# Clock_Schematic_v_3.net
KiCad netlist of a schematic drawn in EAGLE
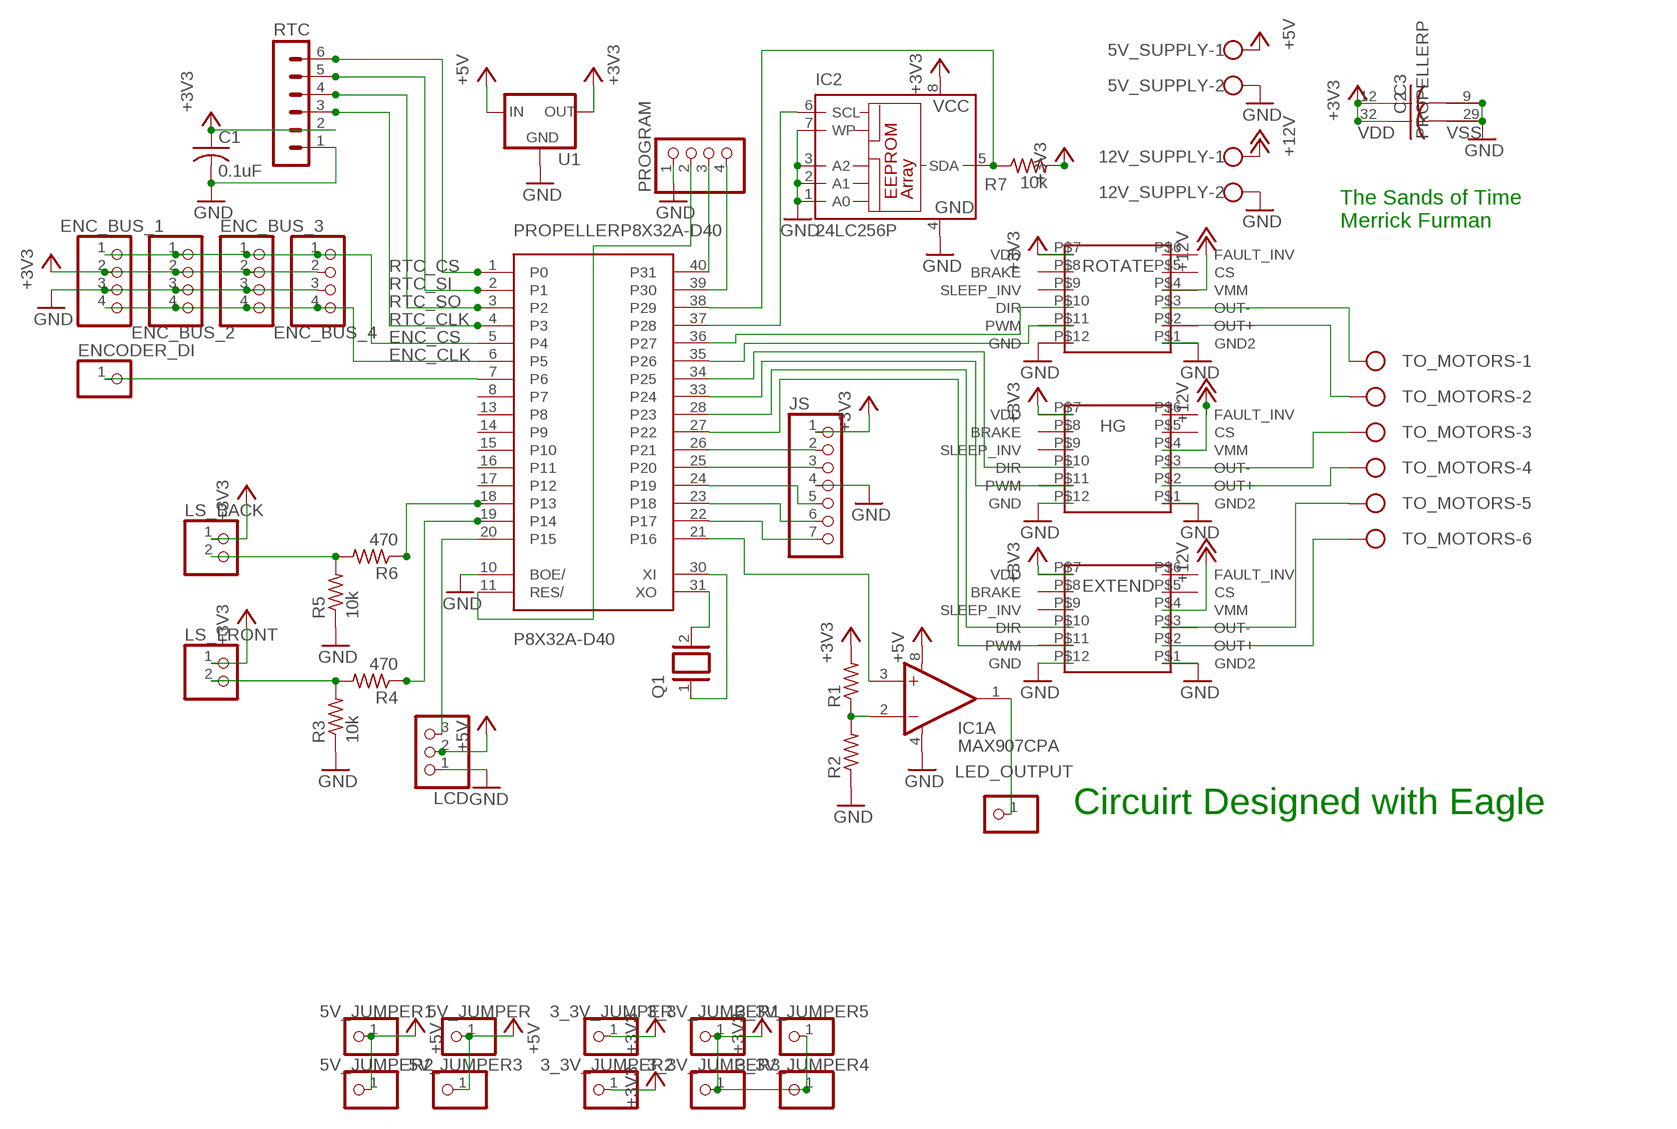
[diagram p0: schematic, sheet 1]

(export (version "E")
  (design (tool "Eeschema 10.0.6"))
  (components
    (comp (ref "3_3V_JUMPER")
      (value "PINHD-1X1")
      (footprint "eagle-import:1X01")
      (libsource (lib "eagle-import") (part "PINHD-1X1"))
    )
    (comp (ref "3_3V_JUMPER1")
      (value "PINHD-1X1")
      (footprint "eagle-import:1X01")
      (libsource (lib "eagle-import") (part "PINHD-1X1"))
    )
    (comp (ref "3_3V_JUMPER2")
      (value "PINHD-1X1")
      (footprint "eagle-import:1X01")
      (libsource (lib "eagle-import") (part "PINHD-1X1"))
    )
    (comp (ref "3_3V_JUMPER3")
      (value "PINHD-1X1")
      (footprint "eagle-import:1X01")
      (libsource (lib "eagle-import") (part "PINHD-1X1"))
    )
    (comp (ref "3_3V_JUMPER4")
      (value "PINHD-1X1")
      (footprint "eagle-import:1X01")
      (libsource (lib "eagle-import") (part "PINHD-1X1"))
    )
    (comp (ref "3_3V_JUMPER5")
      (value "PINHD-1X1")
      (footprint "eagle-import:1X01")
      (libsource (lib "eagle-import") (part "PINHD-1X1"))
    )
    (comp (ref "5V_JUMPER")
      (value "PINHD-1X1")
      (footprint "eagle-import:1X01")
      (libsource (lib "eagle-import") (part "PINHD-1X1"))
    )
    (comp (ref "5V_JUMPER1")
      (value "PINHD-1X1")
      (footprint "eagle-import:1X01")
      (libsource (lib "eagle-import") (part "PINHD-1X1"))
    )
    (comp (ref "5V_JUMPER2")
      (value "PINHD-1X1")
      (footprint "eagle-import:1X01")
      (libsource (lib "eagle-import") (part "PINHD-1X1"))
    )
    (comp (ref "5V_JUMPER3")
      (value "PINHD-1X1")
      (footprint "eagle-import:1X01")
      (libsource (lib "eagle-import") (part "PINHD-1X1"))
    )
    (comp (ref "5V_SUPPLY")
      (value "W237-102")
      (footprint "eagle-import:W237-102")
      (fields (field (name "MPN") "237-102"))
      (libsource (lib "eagle-import") (part "W237-102"))
    )
    (comp (ref "12V_SUPPLY")
      (value "W237-102")
      (footprint "eagle-import:W237-102")
      (fields (field (name "MPN") "237-102"))
      (libsource (lib "eagle-import") (part "W237-102"))
    )
    (comp (ref "C1")
      (value "0.1uF")
      (footprint "eagle-import:C050-025X075")
      (libsource (lib "eagle-import") (part "C-US050-025X075"))
    )
    (comp (ref "C2")
      (value "C-US050-025X075")
      (footprint "eagle-import:C050-025X075")
      (libsource (lib "eagle-import") (part "C-US050-025X075"))
    )
    (comp (ref "C3")
      (value "C-US050-025X075")
      (footprint "eagle-import:C050-025X075")
      (libsource (lib "eagle-import") (part "C-US050-025X075"))
    )
    (comp (ref "ENCODER_DI")
      (value "PINHD-1X1")
      (footprint "eagle-import:1X01")
      (libsource (lib "eagle-import") (part "PINHD-1X1"))
    )
    (comp (ref "ENC_BUS_1")
      (value "PINHD-1X4")
      (footprint "eagle-import:1X04")
      (libsource (lib "eagle-import") (part "PINHD-1X4"))
    )
    (comp (ref "ENC_BUS_2")
      (value "PINHD-1X4")
      (footprint "eagle-import:1X04")
      (libsource (lib "eagle-import") (part "PINHD-1X4"))
    )
    (comp (ref "ENC_BUS_3")
      (value "PINHD-1X4")
      (footprint "eagle-import:1X04")
      (libsource (lib "eagle-import") (part "PINHD-1X4"))
    )
    (comp (ref "ENC_BUS_4")
      (value "PINHD-1X4")
      (footprint "eagle-import:1X04")
      (libsource (lib "eagle-import") (part "PINHD-1X4"))
    )
    (comp (ref "EXTEND")
      (value "DRV")
      (footprint "eagle-import:DRV")
      (libsource (lib "eagle-import") (part "DRV"))
    )
    (comp (ref "HG")
      (value "DRV")
      (footprint "eagle-import:DRV")
      (libsource (lib "eagle-import") (part "DRV"))
    )
    (comp (ref "IC1")
      (value "MAX907CPA")
      (footprint "eagle-import:DIL08")
      (fields (field (name "MF") "MAXIM"))
      (libsource (lib "eagle-import") (part "MAX907CPA"))
    )
    (comp (ref "IC2")
      (value "24LC256P")
      (footprint "eagle-import:DIL8")
      (fields (field (name "MF") "MICROCHIP") (field (name "MPN") "24LC256-E/P"))
      (libsource (lib "eagle-import") (part "24PLC256"))
    )
    (comp (ref "JS")
      (value "PINHD-1X7")
      (footprint "eagle-import:1X07")
      (libsource (lib "eagle-import") (part "PINHD-1X7"))
    )
    (comp (ref "LCD")
      (value "PINHD-1X3")
      (footprint "eagle-import:1X03")
      (libsource (lib "eagle-import") (part "PINHD-1X3"))
    )
    (comp (ref "LED_OUTPUT")
      (value "PINHD-1X1")
      (footprint "eagle-import:1X01")
      (libsource (lib "eagle-import") (part "PINHD-1X1"))
    )
    (comp (ref "LS_BACK")
      (value "PINHD-1X2")
      (footprint "eagle-import:1X02")
      (libsource (lib "eagle-import") (part "PINHD-1X2"))
    )
    (comp (ref "LS_FRONT")
      (value "PINHD-1X2")
      (footprint "eagle-import:1X02")
      (libsource (lib "eagle-import") (part "PINHD-1X2"))
    )
    (comp (ref "PROGRAM")
      (value "PINHD-1X4")
      (footprint "eagle-import:1X04")
      (libsource (lib "eagle-import") (part "PINHD-1X4"))
    )
    (comp (ref "PROPELLER")
      (value "P8X32A-D40")
      (footprint "eagle-import:P8X32A-D40")
      (libsource (lib "eagle-import") (part "P8X32A-D40"))
    )
    (comp (ref "Q1")
      (value "XTAL/S")
      (footprint "eagle-import:QS")
      (libsource (lib "eagle-import") (part "XTAL/S"))
    )
    (comp (ref "R1")
      (value "R-US_0207/10")
      (footprint "eagle-import:0207_10")
      (libsource (lib "eagle-import") (part "R-US_0207/10"))
    )
    (comp (ref "R2")
      (value "R-US_0207/10")
      (footprint "eagle-import:0207_10")
      (libsource (lib "eagle-import") (part "R-US_0207/10"))
    )
    (comp (ref "R3")
      (value "10k")
      (footprint "eagle-import:0207_10")
      (libsource (lib "eagle-import") (part "R-US_0207/10"))
    )
    (comp (ref "R4")
      (value "470")
      (footprint "eagle-import:0207_10")
      (libsource (lib "eagle-import") (part "R-US_0207/10"))
    )
    (comp (ref "R5")
      (value "10k")
      (footprint "eagle-import:0207_10")
      (libsource (lib "eagle-import") (part "R-US_0207/10"))
    )
    (comp (ref "R6")
      (value "470")
      (footprint "eagle-import:0207_10")
      (libsource (lib "eagle-import") (part "R-US_0207/10"))
    )
    (comp (ref "R7")
      (value "10k")
      (footprint "eagle-import:0207_10")
      (libsource (lib "eagle-import") (part "R-US_0207/10"))
    )
    (comp (ref "ROTATE")
      (value "DRV")
      (footprint "eagle-import:DRV")
      (libsource (lib "eagle-import") (part "DRV"))
    )
    (comp (ref "RTC")
      (value "MA06-1")
      (footprint "eagle-import:MA06-1")
      (libsource (lib "eagle-import") (part "MA06-1"))
    )
    (comp (ref "TO_MOTORS")
      (value "W237-6")
      (footprint "eagle-import:W237-6")
      (libsource (lib "eagle-import") (part "W237-6"))
    )
    (comp (ref "U1")
      (value "V_REG_78XXSIDE")
      (footprint "eagle-import:78XXL")
      (libsource (lib "eagle-import") (part "V_REG_78XXSIDE"))
    )
  )
  (nets
    (net (code "1") (name "+3V3") (class "Default")
      (node (ref "3_3V_JUMPER") (pin "1") (pinfunction "1_1") (pintype "passive"))
      (node (ref "3_3V_JUMPER1") (pin "1") (pinfunction "1_1") (pintype "passive"))
      (node (ref "3_3V_JUMPER2") (pin "1") (pinfunction "1_1") (pintype "passive"))
      (node (ref "3_3V_JUMPER3") (pin "1") (pinfunction "1_1") (pintype "passive"))
      (node (ref "3_3V_JUMPER4") (pin "1") (pinfunction "1_1") (pintype "passive"))
      (node (ref "3_3V_JUMPER5") (pin "1") (pinfunction "1_1") (pintype "passive"))
      (node (ref "C1") (pin "1") (pinfunction "1_1") (pintype "passive"))
      (node (ref "C2") (pin "1") (pinfunction "1_1") (pintype "passive"))
      (node (ref "C3") (pin "1") (pinfunction "1_1") (pintype "passive"))
      (node (ref "ENC_BUS_1") (pin "2") (pinfunction "2_2") (pintype "passive"))
      (node (ref "ENC_BUS_2") (pin "2") (pinfunction "2_2") (pintype "passive"))
      (node (ref "ENC_BUS_3") (pin "2") (pinfunction "2_2") (pintype "passive"))
      (node (ref "ENC_BUS_4") (pin "2") (pinfunction "2_2") (pintype "passive"))
      (node (ref "EXTEND") (pin "P$7") (pinfunction "VDD_P$7") (pintype "bidirectional"))
      (node (ref "HG") (pin "P$7") (pinfunction "VDD_P$7") (pintype "bidirectional"))
      (node (ref "IC2") (pin "8") (pinfunction "VCC_8") (pintype "power_in"))
      (node (ref "JS") (pin "1") (pinfunction "1_1") (pintype "passive"))
      (node (ref "LS_BACK") (pin "1") (pinfunction "1_1") (pintype "passive"))
      (node (ref "LS_FRONT") (pin "1") (pinfunction "1_1") (pintype "passive"))
      (node (ref "PROPELLER") (pin "12") (pinfunction "VDD_12") (pintype "power_in"))
      (node (ref "PROPELLER") (pin "32") (pinfunction "VDD_32") (pintype "power_in"))
      (node (ref "R1") (pin "2") (pinfunction "2_2") (pintype "passive"))
      (node (ref "R7") (pin "2") (pinfunction "2_2") (pintype "passive"))
      (node (ref "ROTATE") (pin "P$7") (pinfunction "VDD_P$7") (pintype "bidirectional"))
      (node (ref "RTC") (pin "2") (pinfunction "2_2") (pintype "passive"))
      (node (ref "U1") (pin "OUT") (pinfunction "OUT_OUT") (pintype "passive"))
    )
    (net (code "2") (name "+5V") (class "Default")
      (node (ref "5V_JUMPER") (pin "1") (pinfunction "1_1") (pintype "passive"))
      (node (ref "5V_JUMPER1") (pin "1") (pinfunction "1_1") (pintype "passive"))
      (node (ref "5V_JUMPER2") (pin "1") (pinfunction "1_1") (pintype "passive"))
      (node (ref "5V_JUMPER3") (pin "1") (pinfunction "1_1") (pintype "passive"))
      (node (ref "5V_SUPPLY") (pin "1") (pinfunction "KL_1") (pintype "passive"))
      (node (ref "IC1") (pin "8") (pinfunction "V+_8") (pintype "power_in"))
      (node (ref "LCD") (pin "2") (pinfunction "2_2") (pintype "passive"))
      (node (ref "U1") (pin "IN") (pinfunction "IN_IN") (pintype "input"))
    )
    (net (code "3") (name "+12V") (class "Default")
      (node (ref "12V_SUPPLY") (pin "1") (pinfunction "KL_1") (pintype "passive"))
      (node (ref "EXTEND") (pin "P$4") (pinfunction "VMM_P$4") (pintype "bidirectional"))
      (node (ref "HG") (pin "P$4") (pinfunction "VMM_P$4") (pintype "bidirectional"))
      (node (ref "ROTATE") (pin "P$4") (pinfunction "VMM_P$4") (pintype "bidirectional"))
    )
    (net (code "4") (name "/ENC_CLK") (class "Default")
      (node (ref "ENC_BUS_1") (pin "4") (pinfunction "4_4") (pintype "passive"))
      (node (ref "ENC_BUS_2") (pin "4") (pinfunction "4_4") (pintype "passive"))
      (node (ref "ENC_BUS_3") (pin "4") (pinfunction "4_4") (pintype "passive"))
      (node (ref "ENC_BUS_4") (pin "4") (pinfunction "4_4") (pintype "passive"))
      (node (ref "PROPELLER") (pin "6") (pinfunction "P5_6") (pintype "bidirectional"))
    )
    (net (code "5") (name "/ENC_CS") (class "Default")
      (node (ref "ENC_BUS_1") (pin "1") (pinfunction "1_1") (pintype "passive"))
      (node (ref "ENC_BUS_2") (pin "1") (pinfunction "1_1") (pintype "passive"))
      (node (ref "ENC_BUS_3") (pin "1") (pinfunction "1_1") (pintype "passive"))
      (node (ref "ENC_BUS_4") (pin "1") (pinfunction "1_1") (pintype "passive"))
      (node (ref "PROPELLER") (pin "5") (pinfunction "P4_5") (pintype "bidirectional"))
    )
    (net (code "6") (name "/RTC_CLK") (class "Default")
      (node (ref "PROPELLER") (pin "4") (pinfunction "P3_4") (pintype "bidirectional"))
      (node (ref "RTC") (pin "3") (pinfunction "3_3") (pintype "passive"))
    )
    (net (code "7") (name "/RTC_CS") (class "Default")
      (node (ref "PROPELLER") (pin "1") (pinfunction "P0_1") (pintype "bidirectional"))
      (node (ref "RTC") (pin "6") (pinfunction "6_6") (pintype "passive"))
    )
    (net (code "8") (name "/RTC_SI") (class "Default")
      (node (ref "PROPELLER") (pin "2") (pinfunction "P1_2") (pintype "bidirectional"))
      (node (ref "RTC") (pin "5") (pinfunction "5_5") (pintype "passive"))
    )
    (net (code "9") (name "/RTC_SO") (class "Default")
      (node (ref "PROPELLER") (pin "3") (pinfunction "P2_3") (pintype "bidirectional"))
      (node (ref "RTC") (pin "4") (pinfunction "4_4") (pintype "passive"))
    )
    (net (code "10") (name "GND") (class "Default")
      (node (ref "12V_SUPPLY") (pin "2") (pinfunction "KL_2") (pintype "passive"))
      (node (ref "5V_SUPPLY") (pin "2") (pinfunction "KL_2") (pintype "passive"))
      (node (ref "C1") (pin "2") (pinfunction "2_2") (pintype "passive"))
      (node (ref "C2") (pin "2") (pinfunction "2_2") (pintype "passive"))
      (node (ref "C3") (pin "2") (pinfunction "2_2") (pintype "passive"))
      (node (ref "ENC_BUS_1") (pin "3") (pinfunction "3_3") (pintype "passive"))
      (node (ref "ENC_BUS_2") (pin "3") (pinfunction "3_3") (pintype "passive"))
      (node (ref "ENC_BUS_3") (pin "3") (pinfunction "3_3") (pintype "passive"))
      (node (ref "ENC_BUS_4") (pin "3") (pinfunction "3_3") (pintype "passive"))
      (node (ref "EXTEND") (pin "P$1") (pinfunction "GND2_P$1") (pintype "bidirectional"))
      (node (ref "EXTEND") (pin "P$12") (pinfunction "GND_P$12") (pintype "bidirectional"))
      (node (ref "HG") (pin "P$1") (pinfunction "GND2_P$1") (pintype "bidirectional"))
      (node (ref "HG") (pin "P$12") (pinfunction "GND_P$12") (pintype "bidirectional"))
      (node (ref "IC1") (pin "4") (pinfunction "V-_4") (pintype "power_in"))
      (node (ref "IC2") (pin "1") (pinfunction "A0_1") (pintype "input"))
      (node (ref "IC2") (pin "2") (pinfunction "A1_2") (pintype "input"))
      (node (ref "IC2") (pin "3") (pinfunction "A2_3") (pintype "input"))
      (node (ref "IC2") (pin "4") (pinfunction "GND_4") (pintype "power_in"))
      (node (ref "IC2") (pin "7") (pinfunction "WP_7") (pintype "input"))
      (node (ref "JS") (pin "4") (pinfunction "4_4") (pintype "passive"))
      (node (ref "LCD") (pin "1") (pinfunction "1_1") (pintype "passive"))
      (node (ref "PROGRAM") (pin "1") (pinfunction "1_1") (pintype "passive"))
      (node (ref "PROPELLER") (pin "10") (pinfunction "BOE/_10") (pintype "input"))
      (node (ref "PROPELLER") (pin "29") (pinfunction "VSS_29") (pintype "power_in"))
      (node (ref "PROPELLER") (pin "9") (pinfunction "VSS_9") (pintype "power_in"))
      (node (ref "R2") (pin "1") (pinfunction "1_1") (pintype "passive"))
      (node (ref "R3") (pin "1") (pinfunction "1_1") (pintype "passive"))
      (node (ref "R5") (pin "1") (pinfunction "1_1") (pintype "passive"))
      (node (ref "ROTATE") (pin "P$1") (pinfunction "GND2_P$1") (pintype "bidirectional"))
      (node (ref "ROTATE") (pin "P$12") (pinfunction "GND_P$12") (pintype "bidirectional"))
      (node (ref "RTC") (pin "1") (pinfunction "1_1") (pintype "passive"))
      (node (ref "U1") (pin "GND") (pinfunction "GND_GND") (pintype "input"))
    )
    (net (code "11") (name "Net-(EXTEND-DIR)") (class "Default")
      (node (ref "EXTEND") (pin "P$10") (pinfunction "DIR_P$10") (pintype "bidirectional"))
      (node (ref "PROPELLER") (pin "28") (pinfunction "P23_28") (pintype "bidirectional"))
    )
    (net (code "12") (name "Net-(EXTEND-OUT+)") (class "Default")
      (node (ref "EXTEND") (pin "P$2") (pinfunction "OUT+_P$2") (pintype "bidirectional"))
      (node (ref "TO_MOTORS") (pin "6") (pinfunction "KL_6") (pintype "passive"))
    )
    (net (code "13") (name "Net-(EXTEND-OUT-)") (class "Default")
      (node (ref "EXTEND") (pin "P$3") (pinfunction "OUT-_P$3") (pintype "bidirectional"))
      (node (ref "TO_MOTORS") (pin "5") (pinfunction "KL_5") (pintype "passive"))
    )
    (net (code "14") (name "Net-(EXTEND-PWM)") (class "Default")
      (node (ref "EXTEND") (pin "P$11") (pinfunction "PWM_P$11") (pintype "bidirectional"))
      (node (ref "PROPELLER") (pin "27") (pinfunction "P22_27") (pintype "bidirectional"))
    )
    (net (code "15") (name "Net-(HG-DIR)") (class "Default")
      (node (ref "HG") (pin "P$10") (pinfunction "DIR_P$10") (pintype "bidirectional"))
      (node (ref "PROPELLER") (pin "34") (pinfunction "P25_34") (pintype "bidirectional"))
    )
    (net (code "16") (name "Net-(HG-OUT+)") (class "Default")
      (node (ref "HG") (pin "P$2") (pinfunction "OUT+_P$2") (pintype "bidirectional"))
      (node (ref "TO_MOTORS") (pin "4") (pinfunction "KL_4") (pintype "passive"))
    )
    (net (code "17") (name "Net-(HG-OUT-)") (class "Default")
      (node (ref "HG") (pin "P$3") (pinfunction "OUT-_P$3") (pintype "bidirectional"))
      (node (ref "TO_MOTORS") (pin "3") (pinfunction "KL_3") (pintype "passive"))
    )
    (net (code "18") (name "Net-(HG-PWM)") (class "Default")
      (node (ref "HG") (pin "P$11") (pinfunction "PWM_P$11") (pintype "bidirectional"))
      (node (ref "PROPELLER") (pin "33") (pinfunction "P24_33") (pintype "bidirectional"))
    )
    (net (code "19") (name "Net-(IC1A-+IN)") (class "Default")
      (node (ref "IC1") (pin "3") (pinfunction "+IN_3") (pintype "input"))
      (node (ref "PROPELLER") (pin "21") (pinfunction "P16_21") (pintype "bidirectional"))
    )
    (net (code "20") (name "Net-(IC1A--IN)") (class "Default")
      (node (ref "IC1") (pin "2") (pinfunction "-IN_2") (pintype "input"))
      (node (ref "R1") (pin "1") (pinfunction "1_1") (pintype "passive"))
      (node (ref "R2") (pin "2") (pinfunction "2_2") (pintype "passive"))
    )
    (net (code "21") (name "Net-(IC1A-OUT)") (class "Default")
      (node (ref "IC1") (pin "1") (pinfunction "OUT_1") (pintype "output"))
      (node (ref "LED_OUTPUT") (pin "1") (pinfunction "1_1") (pintype "passive"))
    )
    (net (code "22") (name "Net-(IC2-SCL)") (class "Default")
      (node (ref "IC2") (pin "6") (pinfunction "SCL_6") (pintype "input"))
      (node (ref "PROPELLER") (pin "37") (pinfunction "P28_37") (pintype "bidirectional"))
    )
    (net (code "23") (name "Net-(IC2-SDA)") (class "Default")
      (node (ref "IC2") (pin "5") (pinfunction "SDA_5") (pintype "bidirectional"))
      (node (ref "PROPELLER") (pin "38") (pinfunction "P29_38") (pintype "bidirectional"))
      (node (ref "R7") (pin "1") (pinfunction "1_1") (pintype "passive"))
    )
    (net (code "24") (name "Net-(LS_BACK-Pad2)") (class "Default")
      (node (ref "LS_BACK") (pin "2") (pinfunction "2_2") (pintype "passive"))
      (node (ref "R5") (pin "2") (pinfunction "2_2") (pintype "passive"))
      (node (ref "R6") (pin "2") (pinfunction "2_2") (pintype "passive"))
    )
    (net (code "25") (name "Net-(LS_FRONT-Pad2)") (class "Default")
      (node (ref "LS_FRONT") (pin "2") (pinfunction "2_2") (pintype "passive"))
      (node (ref "R3") (pin "2") (pinfunction "2_2") (pintype "passive"))
      (node (ref "R4") (pin "2") (pinfunction "2_2") (pintype "passive"))
    )
    (net (code "26") (name "Net-(PROPELLERB-P6)") (class "Default")
      (node (ref "ENCODER_DI") (pin "1") (pinfunction "1_1") (pintype "passive"))
      (node (ref "PROPELLER") (pin "7") (pinfunction "P6_7") (pintype "bidirectional"))
    )
    (net (code "27") (name "Net-(PROPELLERB-P13)") (class "Default")
      (node (ref "PROPELLER") (pin "18") (pinfunction "P13_18") (pintype "bidirectional"))
      (node (ref "R6") (pin "1") (pinfunction "1_1") (pintype "passive"))
    )
    (net (code "28") (name "Net-(PROPELLERB-P14)") (class "Default")
      (node (ref "PROPELLER") (pin "19") (pinfunction "P14_19") (pintype "bidirectional"))
      (node (ref "R4") (pin "1") (pinfunction "1_1") (pintype "passive"))
    )
    (net (code "29") (name "Net-(PROPELLERB-P15)") (class "Default")
      (node (ref "LCD") (pin "3") (pinfunction "3_3") (pintype "passive"))
      (node (ref "PROPELLER") (pin "20") (pinfunction "P15_20") (pintype "bidirectional"))
    )
    (net (code "30") (name "Net-(PROPELLERB-P17)") (class "Default")
      (node (ref "JS") (pin "7") (pinfunction "7_7") (pintype "passive"))
      (node (ref "PROPELLER") (pin "22") (pinfunction "P17_22") (pintype "bidirectional"))
    )
    (net (code "31") (name "Net-(PROPELLERB-P18)") (class "Default")
      (node (ref "JS") (pin "6") (pinfunction "6_6") (pintype "passive"))
      (node (ref "PROPELLER") (pin "23") (pinfunction "P18_23") (pintype "bidirectional"))
    )
    (net (code "32") (name "Net-(PROPELLERB-P19)") (class "Default")
      (node (ref "JS") (pin "5") (pinfunction "5_5") (pintype "passive"))
      (node (ref "PROPELLER") (pin "24") (pinfunction "P19_24") (pintype "bidirectional"))
    )
    (net (code "33") (name "Net-(PROPELLERB-P20)") (class "Default")
      (node (ref "JS") (pin "3") (pinfunction "3_3") (pintype "passive"))
      (node (ref "PROPELLER") (pin "25") (pinfunction "P20_25") (pintype "bidirectional"))
    )
    (net (code "34") (name "Net-(PROPELLERB-P21)") (class "Default")
      (node (ref "JS") (pin "2") (pinfunction "2_2") (pintype "passive"))
      (node (ref "PROPELLER") (pin "26") (pinfunction "P21_26") (pintype "bidirectional"))
    )
    (net (code "35") (name "Net-(PROPELLERB-P26)") (class "Default")
      (node (ref "PROPELLER") (pin "35") (pinfunction "P26_35") (pintype "bidirectional"))
      (node (ref "ROTATE") (pin "P$11") (pinfunction "PWM_P$11") (pintype "bidirectional"))
    )
    (net (code "36") (name "Net-(PROPELLERB-P27)") (class "Default")
      (node (ref "PROPELLER") (pin "36") (pinfunction "P27_36") (pintype "bidirectional"))
      (node (ref "ROTATE") (pin "P$10") (pinfunction "DIR_P$10") (pintype "bidirectional"))
    )
    (net (code "37") (name "Net-(PROPELLERB-P30)") (class "Default")
      (node (ref "PROGRAM") (pin "4") (pinfunction "4_4") (pintype "passive"))
      (node (ref "PROPELLER") (pin "39") (pinfunction "P30_39") (pintype "bidirectional"))
    )
    (net (code "38") (name "Net-(PROPELLERB-P31)") (class "Default")
      (node (ref "PROGRAM") (pin "3") (pinfunction "3_3") (pintype "passive"))
      (node (ref "PROPELLER") (pin "40") (pinfunction "P31_40") (pintype "bidirectional"))
    )
    (net (code "39") (name "Net-(PROPELLERB-RES{slash})") (class "Default")
      (node (ref "PROGRAM") (pin "2") (pinfunction "2_2") (pintype "passive"))
      (node (ref "PROPELLER") (pin "11") (pinfunction "RES/_11") (pintype "bidirectional"))
    )
    (net (code "40") (name "Net-(PROPELLERB-XI)") (class "Default")
      (node (ref "PROPELLER") (pin "30") (pinfunction "XI_30") (pintype "input"))
      (node (ref "Q1") (pin "1") (pinfunction "1_1") (pintype "passive"))
    )
    (net (code "41") (name "Net-(PROPELLERB-XO)") (class "Default")
      (node (ref "PROPELLER") (pin "31") (pinfunction "XO_31") (pintype "output"))
      (node (ref "Q1") (pin "2") (pinfunction "2_2") (pintype "passive"))
    )
    (net (code "42") (name "Net-(ROTATE-OUT+)") (class "Default")
      (node (ref "ROTATE") (pin "P$2") (pinfunction "OUT+_P$2") (pintype "bidirectional"))
      (node (ref "TO_MOTORS") (pin "2") (pinfunction "KL_2") (pintype "passive"))
    )
    (net (code "43") (name "Net-(ROTATE-OUT-)") (class "Default")
      (node (ref "ROTATE") (pin "P$3") (pinfunction "OUT-_P$3") (pintype "bidirectional"))
      (node (ref "TO_MOTORS") (pin "1") (pinfunction "KL_1") (pintype "passive"))
    )
    (net (code "44") (name "unconnected-(EXTEND-BRAKE-PadP$8)") (class "Default")
      (node (ref "EXTEND") (pin "P$8") (pinfunction "BRAKE_P$8") (pintype "bidirectional"))
    )
    (net (code "45") (name "unconnected-(EXTEND-CS-PadP$5)") (class "Default")
      (node (ref "EXTEND") (pin "P$5") (pinfunction "CS_P$5") (pintype "bidirectional"))
    )
    (net (code "46") (name "unconnected-(EXTEND-FAULT_INV-PadP$6)") (class "Default")
      (node (ref "EXTEND") (pin "P$6") (pinfunction "FAULT_INV_P$6") (pintype "bidirectional"))
    )
    (net (code "47") (name "unconnected-(EXTEND-SLEEP_INV-PadP$9)") (class "Default")
      (node (ref "EXTEND") (pin "P$9") (pinfunction "SLEEP_INV_P$9") (pintype "bidirectional"))
    )
    (net (code "48") (name "unconnected-(HG-BRAKE-PadP$8)") (class "Default")
      (node (ref "HG") (pin "P$8") (pinfunction "BRAKE_P$8") (pintype "bidirectional"))
    )
    (net (code "49") (name "unconnected-(HG-CS-PadP$5)") (class "Default")
      (node (ref "HG") (pin "P$5") (pinfunction "CS_P$5") (pintype "bidirectional"))
    )
    (net (code "50") (name "unconnected-(HG-FAULT_INV-PadP$6)") (class "Default")
      (node (ref "HG") (pin "P$6") (pinfunction "FAULT_INV_P$6") (pintype "bidirectional"))
    )
    (net (code "51") (name "unconnected-(HG-SLEEP_INV-PadP$9)") (class "Default")
      (node (ref "HG") (pin "P$9") (pinfunction "SLEEP_INV_P$9") (pintype "bidirectional"))
    )
    (net (code "52") (name "unconnected-(PROPELLERB-P7-Pad8)") (class "Default")
      (node (ref "PROPELLER") (pin "8") (pinfunction "P7_8") (pintype "bidirectional"))
    )
    (net (code "53") (name "unconnected-(PROPELLERB-P8-Pad13)") (class "Default")
      (node (ref "PROPELLER") (pin "13") (pinfunction "P8_13") (pintype "bidirectional"))
    )
    (net (code "54") (name "unconnected-(PROPELLERB-P9-Pad14)") (class "Default")
      (node (ref "PROPELLER") (pin "14") (pinfunction "P9_14") (pintype "bidirectional"))
    )
    (net (code "55") (name "unconnected-(PROPELLERB-P10-Pad15)") (class "Default")
      (node (ref "PROPELLER") (pin "15") (pinfunction "P10_15") (pintype "bidirectional"))
    )
    (net (code "56") (name "unconnected-(PROPELLERB-P11-Pad16)") (class "Default")
      (node (ref "PROPELLER") (pin "16") (pinfunction "P11_16") (pintype "bidirectional"))
    )
    (net (code "57") (name "unconnected-(PROPELLERB-P12-Pad17)") (class "Default")
      (node (ref "PROPELLER") (pin "17") (pinfunction "P12_17") (pintype "bidirectional"))
    )
    (net (code "58") (name "unconnected-(ROTATE-BRAKE-PadP$8)") (class "Default")
      (node (ref "ROTATE") (pin "P$8") (pinfunction "BRAKE_P$8") (pintype "bidirectional"))
    )
    (net (code "59") (name "unconnected-(ROTATE-CS-PadP$5)") (class "Default")
      (node (ref "ROTATE") (pin "P$5") (pinfunction "CS_P$5") (pintype "bidirectional"))
    )
    (net (code "60") (name "unconnected-(ROTATE-FAULT_INV-PadP$6)") (class "Default")
      (node (ref "ROTATE") (pin "P$6") (pinfunction "FAULT_INV_P$6") (pintype "bidirectional"))
    )
    (net (code "61") (name "unconnected-(ROTATE-SLEEP_INV-PadP$9)") (class "Default")
      (node (ref "ROTATE") (pin "P$9") (pinfunction "SLEEP_INV_P$9") (pintype "bidirectional"))
    )
  )
)
